# Adafruit_MLX90640_IR_Thermal_Camera.net
KiCad netlist of a schematic drawn in EAGLE
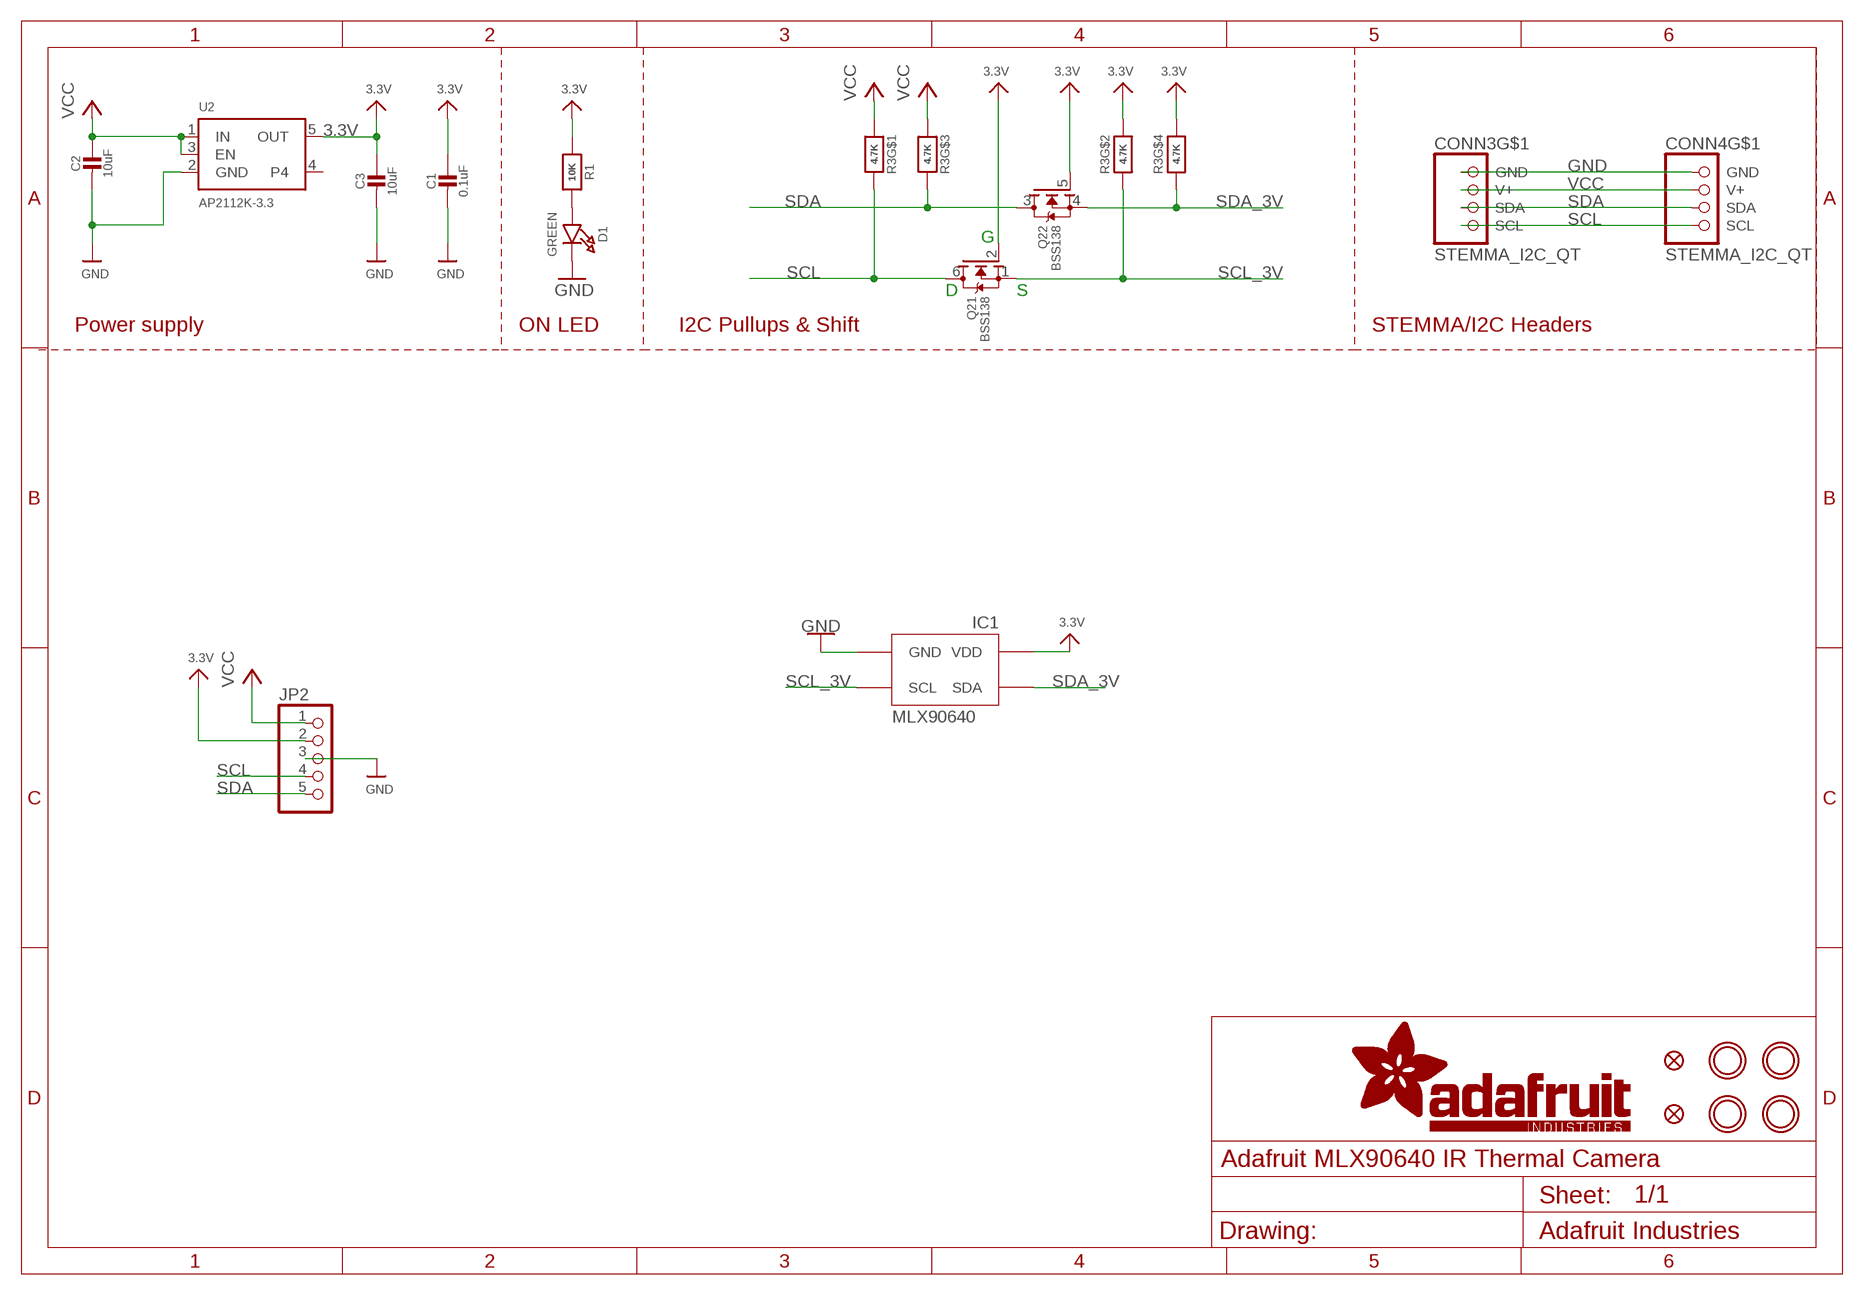
[diagram p0: schematic, sheet 1]

(export (version "E")
  (design (tool "Eeschema 10.0.6"))
  (components
    (comp (ref "C1")
      (value "0.1uF")
      (footprint "eagle-import:0603-NO")
      (libsource (lib "eagle-import") (part "CAP_CERAMIC0603_NO"))
    )
    (comp (ref "C2")
      (value "10uF")
      (footprint "eagle-import:0805-NO")
      (libsource (lib "eagle-import") (part "CAP_CERAMIC0805-NOOUTLINE"))
    )
    (comp (ref "C3")
      (value "10uF")
      (footprint "eagle-import:0805-NO")
      (libsource (lib "eagle-import") (part "CAP_CERAMIC0805-NOOUTLINE"))
    )
    (comp (ref "CONN3")
      (value "STEMMA_I2C_QT")
      (footprint "eagle-import:JST_SH4")
      (libsource (lib "eagle-import") (part "STEMMA_I2C_QT"))
    )
    (comp (ref "CONN4")
      (value "STEMMA_I2C_QT")
      (footprint "eagle-import:JST_SH4")
      (libsource (lib "eagle-import") (part "STEMMA_I2C_QT"))
    )
    (comp (ref "D1")
      (value "GREEN")
      (footprint "eagle-import:CHIPLED_0603_NOOUTLINE")
      (libsource (lib "eagle-import") (part "LED0603_NOOUTLINE"))
    )
    (comp (ref "FID3")
      (value "FIDUCIAL_1MM")
      (footprint "eagle-import:FIDUCIAL_1MM")
      (libsource (lib "eagle-import") (part "FIDUCIAL_1MM"))
    )
    (comp (ref "FID4")
      (value "FIDUCIAL_1MM")
      (footprint "eagle-import:FIDUCIAL_1MM")
      (libsource (lib "eagle-import") (part "FIDUCIAL_1MM"))
    )
    (comp (ref "IC1")
      (value "MLX90640")
      (footprint "eagle-import:MLX90640")
      (libsource (lib "eagle-import") (part "MLX90640"))
    )
    (comp (ref "JP2")
      (value "HEADER-1X5ROUND")
      (footprint "eagle-import:1X05_ROUND")
      (libsource (lib "eagle-import") (part "HEADER-1X5ROUND"))
    )
    (comp (ref "Q2")
      (value "BSS138")
      (footprint "eagle-import:SOT363")
      (libsource (lib "eagle-import") (part "MOSFET-N_DUAL"))
    )
    (comp (ref "R1")
      (value "10K")
      (footprint "eagle-import:0603-NO")
      (libsource (lib "eagle-import") (part "RESISTOR_0603_NOOUT"))
    )
    (comp (ref "R3")
      (value "4.7K")
      (footprint "eagle-import:RESPACK_4X0603")
      (libsource (lib "eagle-import") (part "RESISTOR_4PACK"))
    )
    (comp (ref "U$1")
      (value "MOUNTINGHOLE2.5")
      (footprint "eagle-import:MOUNTINGHOLE_2.5_PLATED")
      (libsource (lib "eagle-import") (part "MOUNTINGHOLE2.5"))
    )
    (comp (ref "U$17")
      (value "MOUNTINGHOLE2.5")
      (footprint "eagle-import:MOUNTINGHOLE_2.5_PLATED")
      (libsource (lib "eagle-import") (part "MOUNTINGHOLE2.5"))
    )
    (comp (ref "U$19")
      (value "MOUNTINGHOLE2.5")
      (footprint "eagle-import:MOUNTINGHOLE_2.5_PLATED")
      (libsource (lib "eagle-import") (part "MOUNTINGHOLE2.5"))
    )
    (comp (ref "U$21")
      (value "MOUNTINGHOLE2.5")
      (footprint "eagle-import:MOUNTINGHOLE_2.5_PLATED")
      (libsource (lib "eagle-import") (part "MOUNTINGHOLE2.5"))
    )
    (comp (ref "U2")
      (value "AP2112K-3.3")
      (footprint "eagle-import:SOT23-5")
      (libsource (lib "eagle-import") (part "VREG_SOT23-5"))
    )
  )
  (nets
    (net (code "1") (name "/SCL") (class "Default")
      (node (ref "CONN3") (pin "4") (pinfunction "SCL_4") (pintype "passive"))
      (node (ref "CONN4") (pin "4") (pinfunction "SCL_4") (pintype "passive"))
      (node (ref "JP2") (pin "4") (pinfunction "4_4") (pintype "passive"))
      (node (ref "Q2") (pin "6") (pinfunction "D_6") (pintype "bidirectional"))
      (node (ref "R3") (pin "8") (pinfunction "2_8") (pintype "passive"))
    )
    (net (code "2") (name "/SCL_3V") (class "Default")
      (node (ref "IC1") (pin "SCL") (pinfunction "SCL_SCL") (pintype "bidirectional"))
      (node (ref "Q2") (pin "1") (pinfunction "S_1") (pintype "bidirectional"))
      (node (ref "R3") (pin "7") (pinfunction "2_7") (pintype "passive"))
    )
    (net (code "3") (name "/SDA") (class "Default")
      (node (ref "CONN3") (pin "3") (pinfunction "SDA_3") (pintype "passive"))
      (node (ref "CONN4") (pin "3") (pinfunction "SDA_3") (pintype "passive"))
      (node (ref "JP2") (pin "5") (pinfunction "5_5") (pintype "passive"))
      (node (ref "Q2") (pin "3") (pinfunction "D_3") (pintype "bidirectional"))
      (node (ref "R3") (pin "6") (pinfunction "2_6") (pintype "passive"))
    )
    (net (code "4") (name "/SDA_3V") (class "Default")
      (node (ref "IC1") (pin "SDA") (pinfunction "SDA_SDA") (pintype "bidirectional"))
      (node (ref "Q2") (pin "4") (pinfunction "S_4") (pintype "bidirectional"))
      (node (ref "R3") (pin "5") (pinfunction "2_5") (pintype "passive"))
    )
    (net (code "5") (name "3.3V") (class "Default")
      (node (ref "C1") (pin "1") (pinfunction "1_1") (pintype "passive"))
      (node (ref "C3") (pin "1") (pinfunction "1_1") (pintype "passive"))
      (node (ref "IC1") (pin "VDD") (pinfunction "VDD_VDD") (pintype "power_in"))
      (node (ref "JP2") (pin "2") (pinfunction "2_2") (pintype "passive"))
      (node (ref "Q2") (pin "2") (pinfunction "G_2") (pintype "bidirectional"))
      (node (ref "Q2") (pin "5") (pinfunction "G_5") (pintype "bidirectional"))
      (node (ref "R1") (pin "1") (pinfunction "1_1") (pintype "passive"))
      (node (ref "R3") (pin "2") (pinfunction "1_2") (pintype "passive"))
      (node (ref "R3") (pin "4") (pinfunction "1_4") (pintype "passive"))
      (node (ref "U2") (pin "5") (pinfunction "OUT_5") (pintype "power_in"))
    )
    (net (code "6") (name "GND") (class "Default")
      (node (ref "C1") (pin "2") (pinfunction "2_2") (pintype "passive"))
      (node (ref "C2") (pin "2") (pinfunction "2_2") (pintype "passive"))
      (node (ref "C3") (pin "2") (pinfunction "2_2") (pintype "passive"))
      (node (ref "CONN3") (pin "1") (pinfunction "GND_1") (pintype "passive"))
      (node (ref "CONN4") (pin "1") (pinfunction "GND_1") (pintype "passive"))
      (node (ref "D1") (pin "C") (pinfunction "C_C") (pintype "passive"))
      (node (ref "IC1") (pin "GND") (pinfunction "GND_GND") (pintype "power_in"))
      (node (ref "JP2") (pin "3") (pinfunction "3_3") (pintype "passive"))
      (node (ref "U2") (pin "2") (pinfunction "GND_2") (pintype "power_in"))
    )
    (net (code "7") (name "Net-(D1-PadA)") (class "Default")
      (node (ref "D1") (pin "A") (pinfunction "A_A") (pintype "passive"))
      (node (ref "R1") (pin "2") (pinfunction "2_2") (pintype "passive"))
    )
    (net (code "8") (name "VCC") (class "Default")
      (node (ref "C2") (pin "1") (pinfunction "1_1") (pintype "passive"))
      (node (ref "CONN3") (pin "2") (pinfunction "V+_2") (pintype "passive"))
      (node (ref "CONN4") (pin "2") (pinfunction "V+_2") (pintype "passive"))
      (node (ref "JP2") (pin "1") (pinfunction "1_1") (pintype "passive"))
      (node (ref "R3") (pin "1") (pinfunction "1_1") (pintype "passive"))
      (node (ref "R3") (pin "3") (pinfunction "1_3") (pintype "passive"))
      (node (ref "U2") (pin "1") (pinfunction "IN_1") (pintype "power_in"))
      (node (ref "U2") (pin "3") (pinfunction "EN_3") (pintype "input"))
    )
    (net (code "9") (name "unconnected-(U2-P4-Pad4)") (class "Default")
      (node (ref "U2") (pin "4") (pinfunction "P4_4") (pintype "bidirectional"))
    )
  )
)
